# UV_LED_IPEX4.net
KiCad netlist of a schematic drawn in EasyEDA
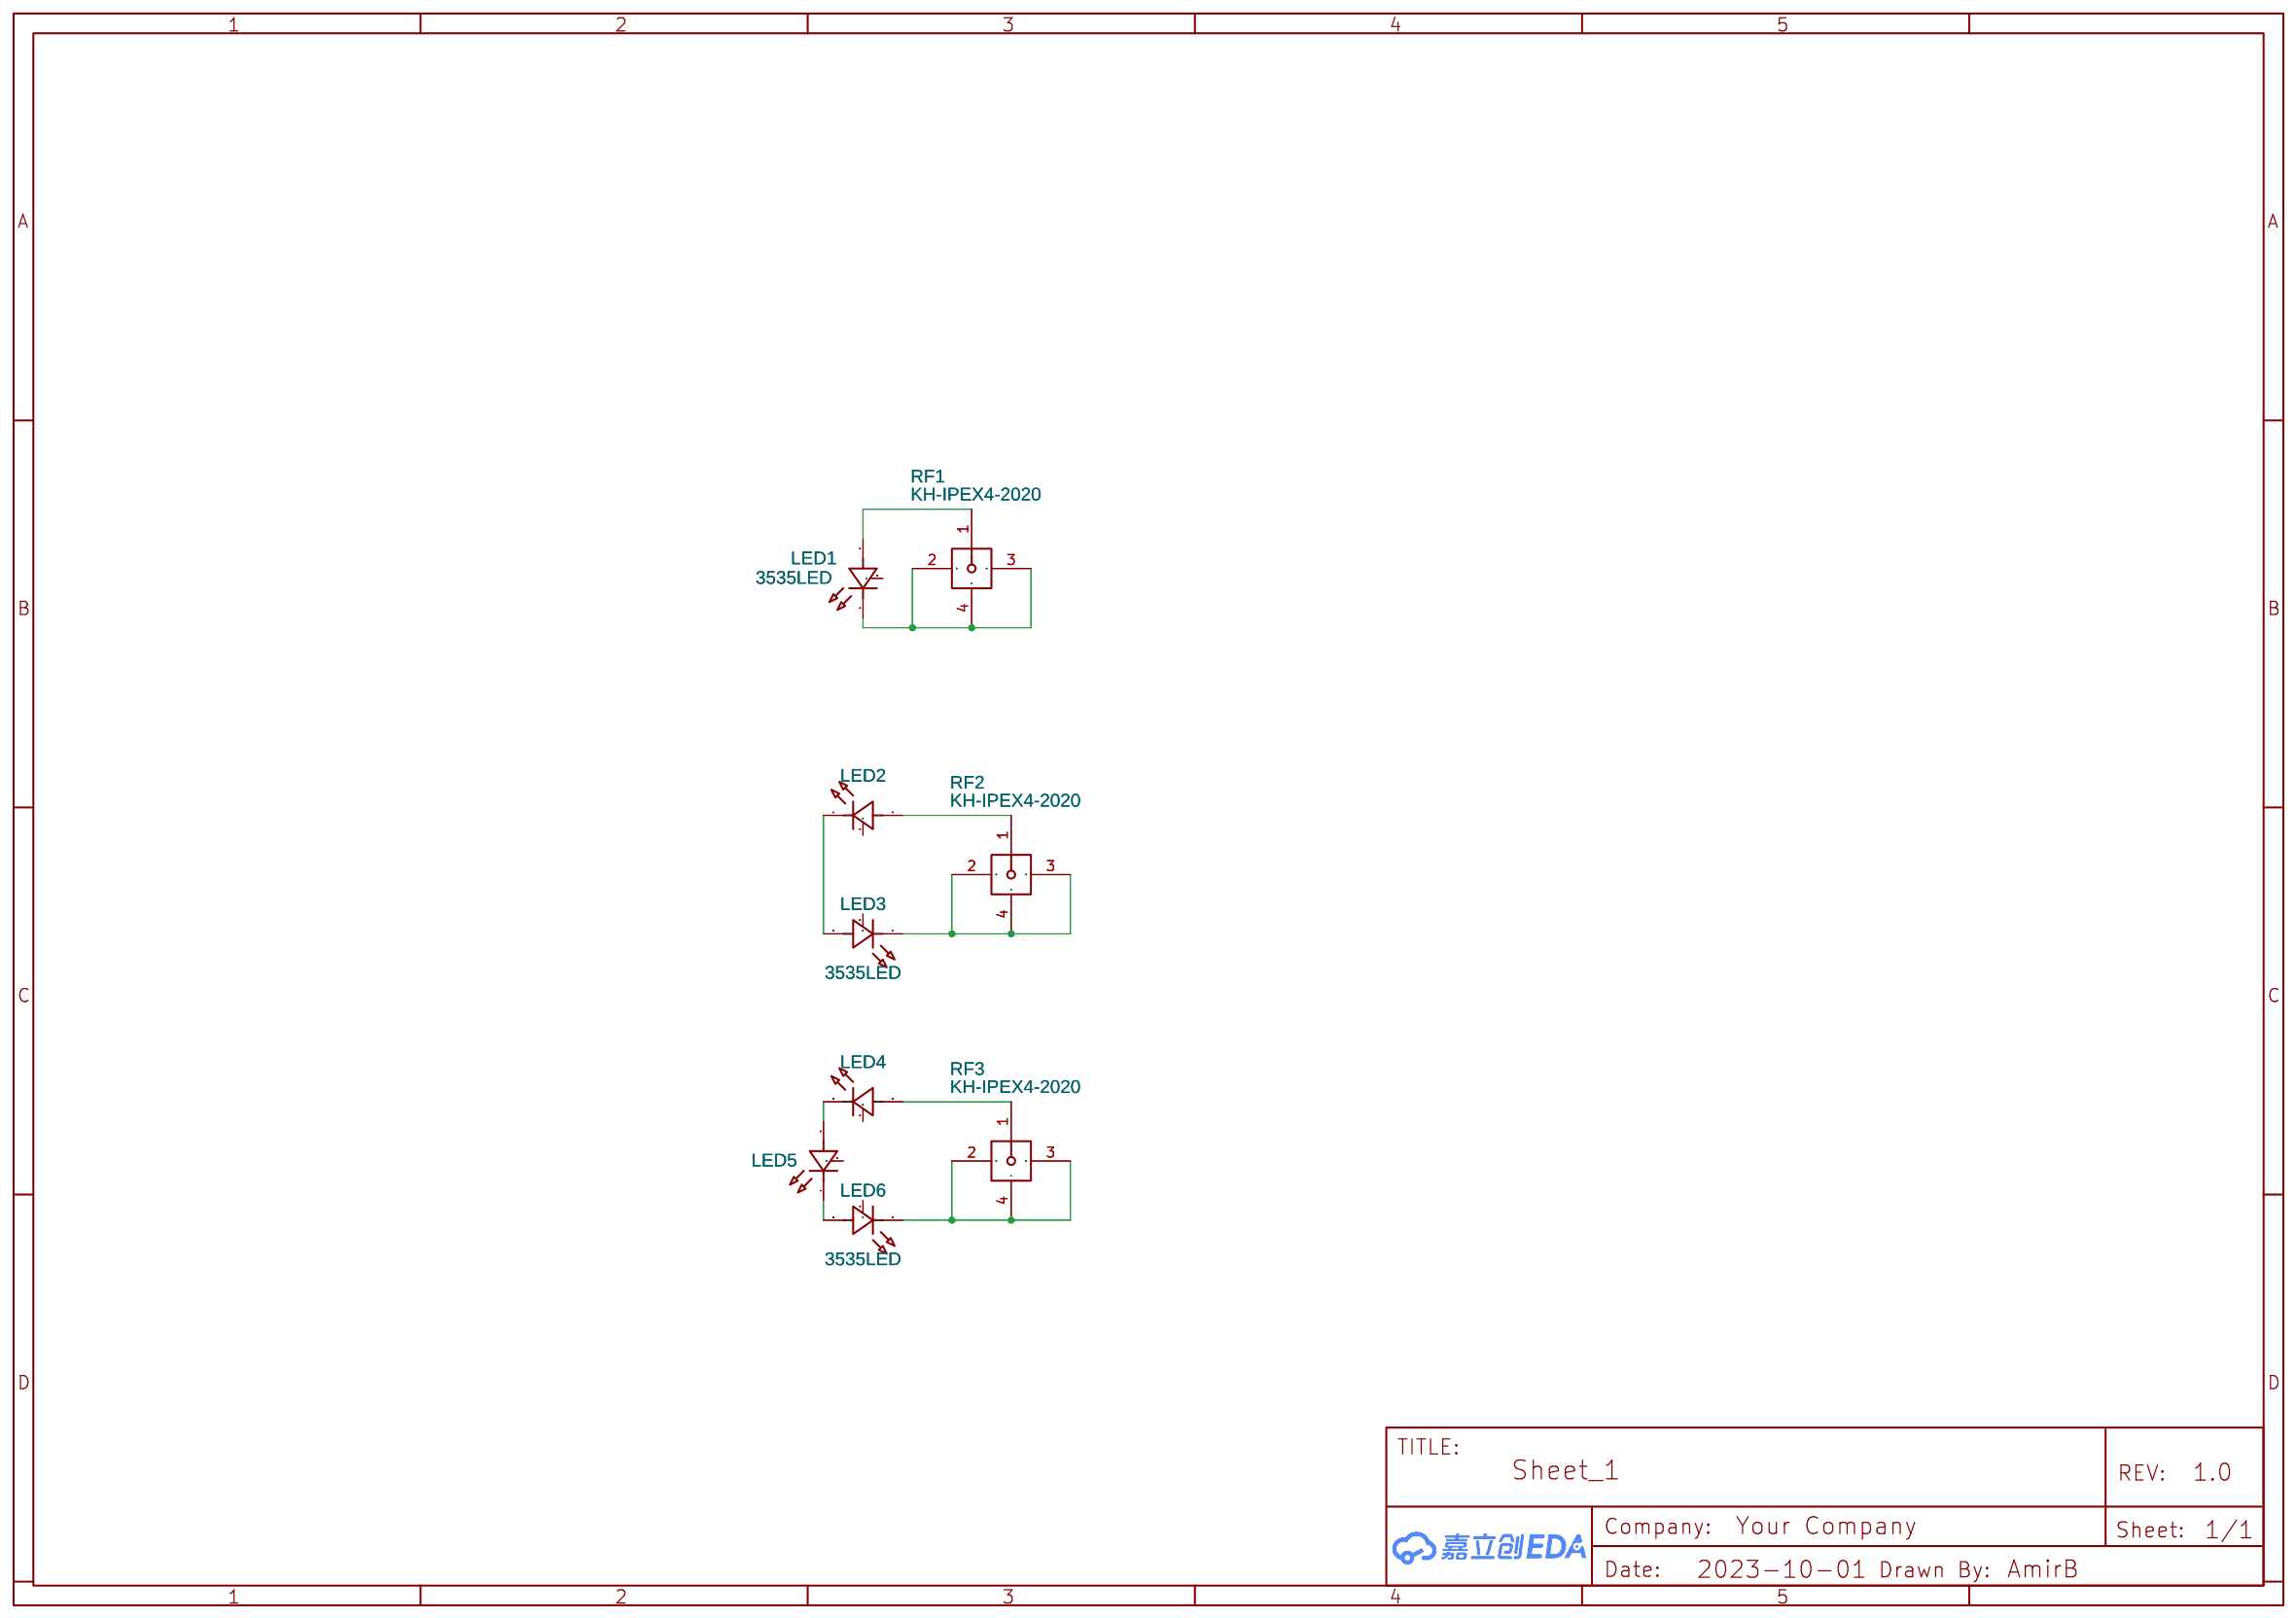
[diagram p0: schematic sheet]

(export (version "E")
  (design (tool "Eeschema 10.0.6"))
  (components
    (comp (ref "LED1")
      (value "3535LED")
      (fields
        (field (name "BOM_Manufacturer Part") "M3535N1UVS8U06-365nm")
        (field (name "BOM_Supplier Part") "C2833503")
      )
      (libsource (lib "") (part "M3535N1UVS8U06-365NM"))
    )
    (comp (ref "LED2")
      (value "3535LED")
      (fields
        (field (name "BOM_Manufacturer Part") "M3535N1UVS8U06-365nm")
        (field (name "BOM_Supplier Part") "C2833503")
      )
      (libsource (lib "") (part "M3535N1UVS8U06-365NM_2"))
    )
    (comp (ref "LED3")
      (value "3535LED")
      (fields
        (field (name "BOM_Manufacturer Part") "M3535N1UVS8U06-365nm")
        (field (name "BOM_Supplier Part") "C2833503")
      )
      (libsource (lib "") (part "M3535N1UVS8U06-365NM_1"))
    )
    (comp (ref "LED4")
      (value "3535LED")
      (fields
        (field (name "BOM_Manufacturer Part") "M3535N1UVS8U06-365nm")
        (field (name "BOM_Supplier Part") "C2833503")
      )
      (libsource (lib "") (part "M3535N1UVS8U06-365NM_2"))
    )
    (comp (ref "LED5")
      (value "3535LED")
      (fields
        (field (name "BOM_Manufacturer Part") "M3535N1UVS8U06-365nm")
        (field (name "BOM_Supplier Part") "C2833503")
      )
      (libsource (lib "") (part "M3535N1UVS8U06-365NM"))
    )
    (comp (ref "LED6")
      (value "3535LED")
      (fields
        (field (name "BOM_Manufacturer Part") "M3535N1UVS8U06-365nm")
        (field (name "BOM_Supplier Part") "C2833503")
      )
      (libsource (lib "") (part "M3535N1UVS8U06-365NM_1"))
    )
    (comp (ref "RF1")
      (value "KH-IPEX4-2020")
      (fields (field (name "Manufacturer") "kinghelm(金航标)"))
      (libsource (lib "") (part "KH-IPEX4-2020"))
    )
    (comp (ref "RF2")
      (value "KH-IPEX4-2020")
      (fields (field (name "Manufacturer") "kinghelm(金航标)"))
      (libsource (lib "") (part "KH-IPEX4-2020"))
    )
    (comp (ref "RF3")
      (value "KH-IPEX4-2020")
      (fields (field (name "Manufacturer") "kinghelm(金航标)"))
      (libsource (lib "") (part "KH-IPEX4-2020"))
    )
  )
  (nets
    (net (code "1") (name "Net-(LED1-A)") (class "Default")
      (node (ref "LED1") (pin "2") (pinfunction "A_2") (pintype "unspecified"))
      (node (ref "RF1") (pin "1") (pinfunction "1_1") (pintype "unspecified"))
    )
    (net (code "2") (name "Net-(LED1-K)") (class "Default")
      (node (ref "LED1") (pin "1") (pinfunction "K_1") (pintype "unspecified"))
      (node (ref "RF1") (pin "2") (pinfunction "2_2") (pintype "unspecified"))
      (node (ref "RF1") (pin "3") (pinfunction "3_3") (pintype "unspecified"))
      (node (ref "RF1") (pin "4") (pinfunction "4_4") (pintype "unspecified"))
    )
    (net (code "3") (name "Net-(LED2-A)") (class "Default")
      (node (ref "LED2") (pin "2") (pinfunction "A_2") (pintype "unspecified"))
      (node (ref "RF2") (pin "1") (pinfunction "1_1") (pintype "unspecified"))
    )
    (net (code "4") (name "Net-(LED2-K)") (class "Default")
      (node (ref "LED2") (pin "1") (pinfunction "K_1") (pintype "unspecified"))
      (node (ref "LED3") (pin "2") (pinfunction "A_2") (pintype "unspecified"))
    )
    (net (code "5") (name "Net-(LED3-K)") (class "Default")
      (node (ref "LED3") (pin "1") (pinfunction "K_1") (pintype "unspecified"))
      (node (ref "RF2") (pin "2") (pinfunction "2_2") (pintype "unspecified"))
      (node (ref "RF2") (pin "3") (pinfunction "3_3") (pintype "unspecified"))
      (node (ref "RF2") (pin "4") (pinfunction "4_4") (pintype "unspecified"))
    )
    (net (code "6") (name "Net-(LED4-A)") (class "Default")
      (node (ref "LED4") (pin "2") (pinfunction "A_2") (pintype "unspecified"))
      (node (ref "RF3") (pin "1") (pinfunction "1_1") (pintype "unspecified"))
    )
    (net (code "7") (name "Net-(LED4-K)") (class "Default")
      (node (ref "LED4") (pin "1") (pinfunction "K_1") (pintype "unspecified"))
      (node (ref "LED5") (pin "2") (pinfunction "A_2") (pintype "unspecified"))
    )
    (net (code "8") (name "Net-(LED5-K)") (class "Default")
      (node (ref "LED5") (pin "1") (pinfunction "K_1") (pintype "unspecified"))
      (node (ref "LED6") (pin "2") (pinfunction "A_2") (pintype "unspecified"))
    )
    (net (code "9") (name "Net-(LED6-K)") (class "Default")
      (node (ref "LED6") (pin "1") (pinfunction "K_1") (pintype "unspecified"))
      (node (ref "RF3") (pin "2") (pinfunction "2_2") (pintype "unspecified"))
      (node (ref "RF3") (pin "3") (pinfunction "3_3") (pintype "unspecified"))
      (node (ref "RF3") (pin "4") (pinfunction "4_4") (pintype "unspecified"))
    )
    (net (code "10") (name "unconnected-(LED1-Pad3)") (class "Default")
      (node (ref "LED1") (pin "3") (pinfunction "3_3") (pintype "unspecified"))
    )
    (net (code "11") (name "unconnected-(LED2-Pad3)") (class "Default")
      (node (ref "LED2") (pin "3") (pinfunction "3_3") (pintype "unspecified"))
    )
    (net (code "12") (name "unconnected-(LED3-Pad3)") (class "Default")
      (node (ref "LED3") (pin "3") (pinfunction "3_3") (pintype "unspecified"))
    )
    (net (code "13") (name "unconnected-(LED4-Pad3)") (class "Default")
      (node (ref "LED4") (pin "3") (pinfunction "3_3") (pintype "unspecified"))
    )
    (net (code "14") (name "unconnected-(LED5-Pad3)") (class "Default")
      (node (ref "LED5") (pin "3") (pinfunction "3_3") (pintype "unspecified"))
    )
    (net (code "15") (name "unconnected-(LED6-Pad3)") (class "Default")
      (node (ref "LED6") (pin "3") (pinfunction "3_3") (pintype "unspecified"))
    )
  )
)
